# Noise.net
KiCad netlist of a schematic drawn in Altium Designer
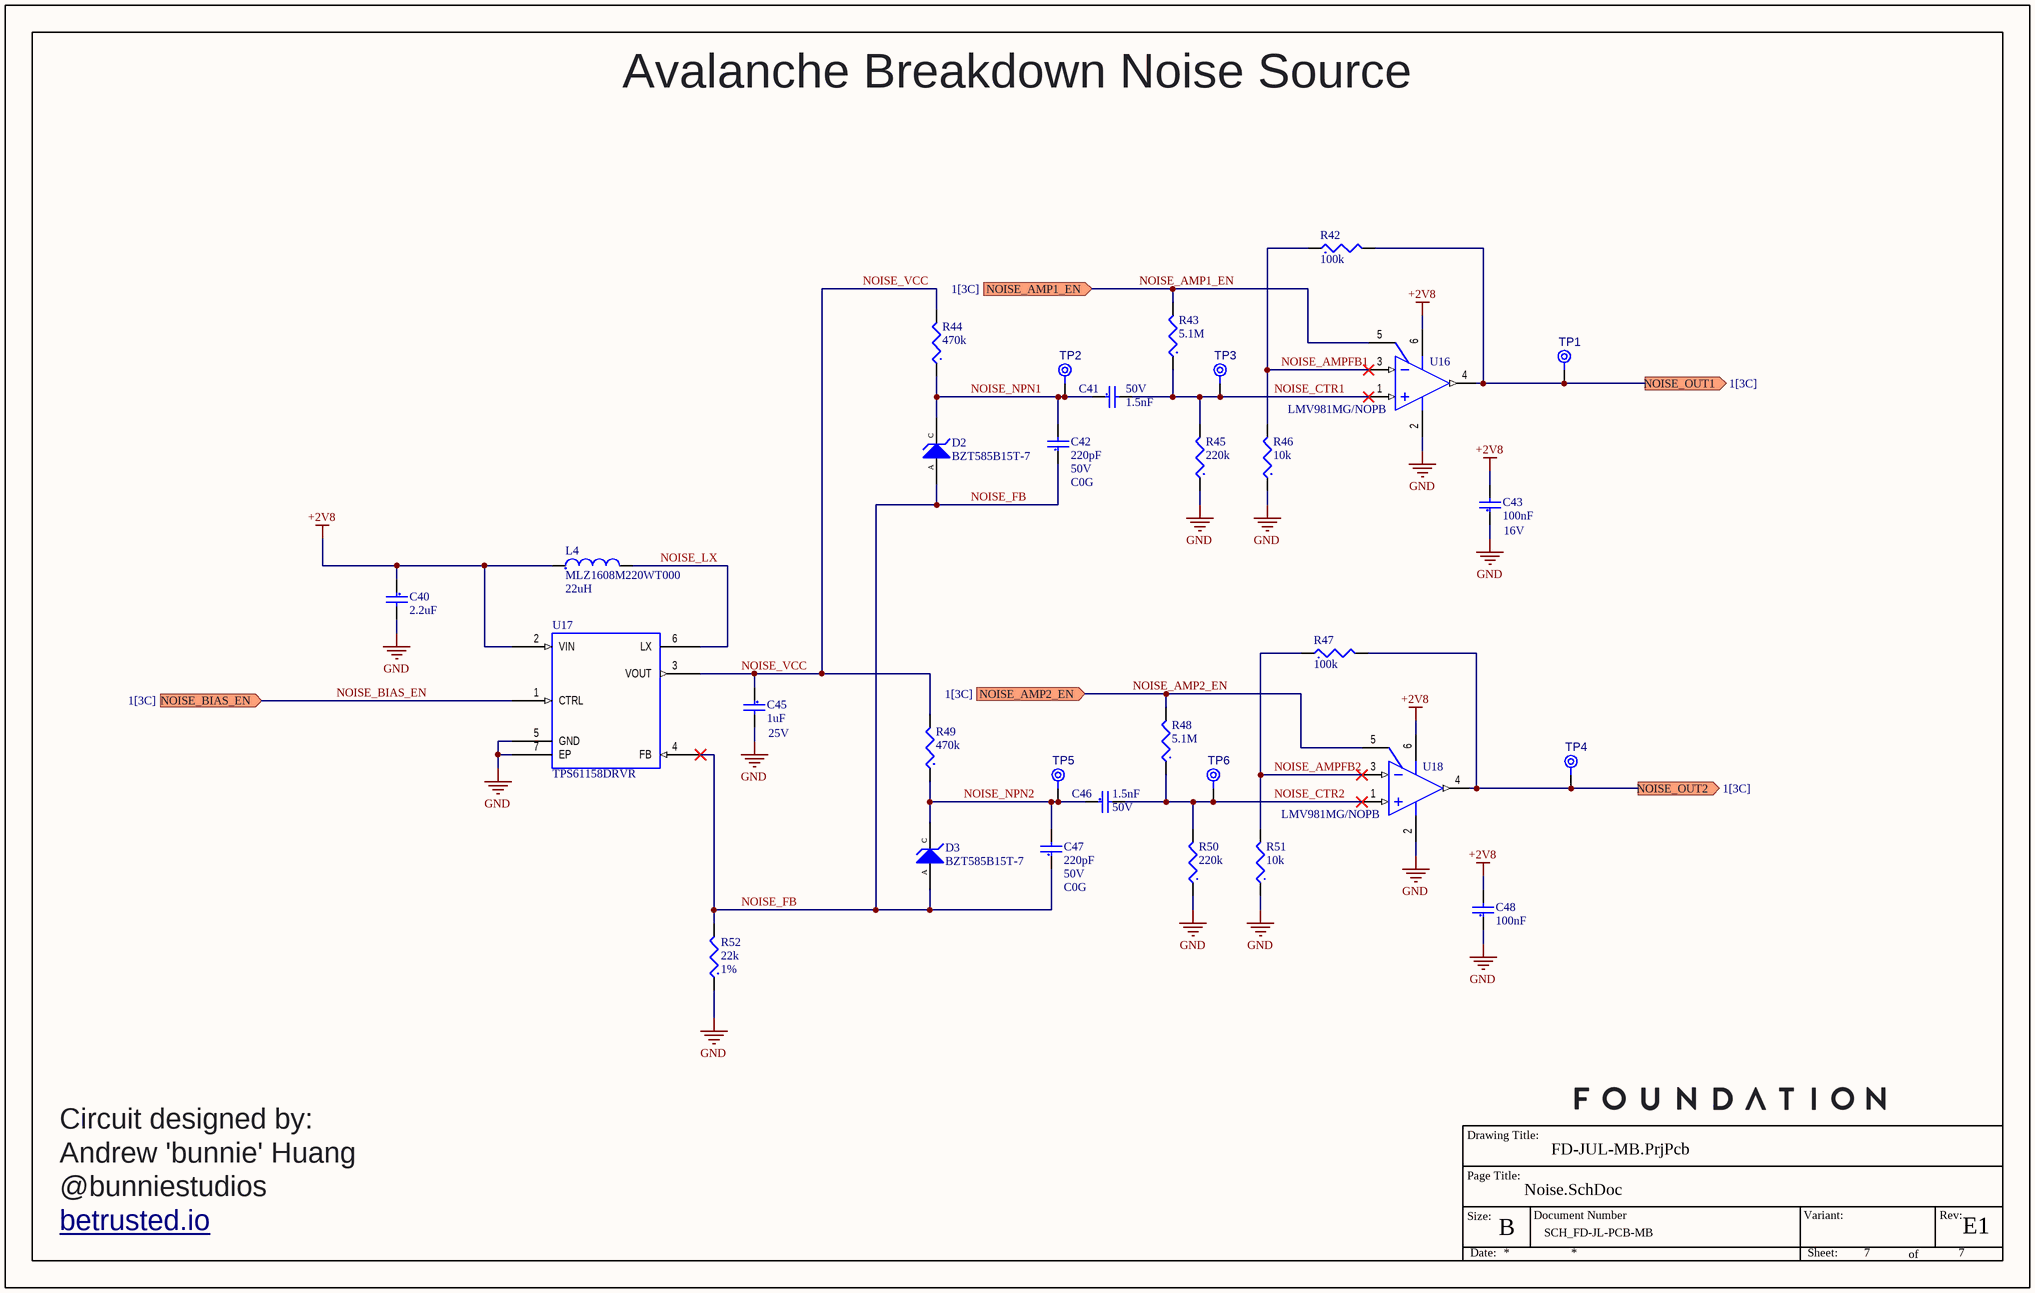
[diagram p0: Noise.SchDoc]

(export (version "E")
  (design (tool "Eeschema 10.0.6"))
  (components
    (comp (ref "C40")
      (value "CAP CER 2.2uF 6.3V 10% X5R 0402")
      (footprint "CAPC0402(1005)55_L")
      (description "2.2µF ±10% 6.3V Ceramic Capacitor X5R 0402 (1005 Metric)")
      (fields (field (name "CAPACITANCE") "2.2uF") (field (name "TOLERANCE") "10%"))
      (libsource (lib "Altium Concord Pro on A365") (part "CAP-NP-2"))
    )
    (comp (ref "C41")
      (value "CAP CER 1500pF 50V 10% X7R 0402")
      (footprint "CAPC0402(1005)55_L")
      (description "1500pF ±10% 50V Ceramic Capacitor X7R 0402 (1005 Metric)")
      (fields
        (field (name "CAPACITANCE") "1.5nF")
        (field (name "VOLTAGE") "50V")
        (field (name "VOLTAGE RATING") "50V")
        (field (name "TOLERANCE") "10%")
      )
      (libsource (lib "Altium Concord Pro on A365") (part "CAP-NP-2"))
    )
    (comp (ref "C42")
      (value "CAP CER 220pF 50V 5% C0G 0402")
      (footprint "CAPC0402(1005)55_L")
      (description "220pF ±5% 50V Ceramic Capacitor C0G, NP0 0402 (1005 Metric)")
      (fields
        (field (name "CAPACITANCE") "220pF")
        (field (name "VOLTAGE") "50V")
        (field (name "DIELECTRIC") "C0G")
        (field (name "TOLERANCE") "5%")
      )
      (libsource (lib "Altium Concord Pro on A365") (part "CAP-NP-2"))
    )
    (comp (ref "C43")
      (value "CAP CER 0.1uF 16V 10% X7R 0402")
      (footprint "CAPC0402(1005)55_L")
      (description "0.1µF ±10% 16V Ceramic Capacitor X7R 0402 (1005 Metric)")
      (fields
        (field (name "CAPACITANCE") "100nF")
        (field (name "VOLTAGE") "16V")
        (field (name "TOLERANCE") "10%")
      )
      (libsource (lib "Altium Concord Pro on A365") (part "CAP-NP-2"))
    )
    (comp (ref "C45")
      (value "CAP CER 1uF 25V 10% X5R 0402")
      (footprint "CAPC0402(1005)55_L")
      (description "±10% 25V Ceramic Capacitor X5R 0402 (1005 Metric)")
      (fields (field (name "CAPACITANCE") "1uF") (field (name "RATED DC VOLTAGE (URDC)") "25V"))
      (libsource (lib "Altium Concord Pro on A365") (part "CAP-NP-2"))
    )
    (comp (ref "C46")
      (value "CAP CER 1500pF 50V 10% X7R 0402")
      (footprint "CAPC0402(1005)55_L")
      (description "1500pF ±10% 50V Ceramic Capacitor X7R 0402 (1005 Metric)")
      (fields
        (field (name "CAPACITANCE") "1.5nF")
        (field (name "VOLTAGE") "50V")
        (field (name "TOLERANCE") "10%")
      )
      (libsource (lib "Altium Concord Pro on A365") (part "CAP-NP-2"))
    )
    (comp (ref "C47")
      (value "CAP CER 220pF 50V 5% C0G 0402")
      (footprint "CAPC0402(1005)55_L")
      (description "220pF ±5% 50V Ceramic Capacitor C0G, NP0 0402 (1005 Metric)")
      (fields
        (field (name "CAPACITANCE") "220pF")
        (field (name "VOLTAGE") "50V")
        (field (name "DIELECTRIC") "C0G")
        (field (name "TOLERANCE") "5%")
      )
      (libsource (lib "Altium Concord Pro on A365") (part "CAP-NP-2"))
    )
    (comp (ref "C48")
      (value "CAP CER 0.1uF 16V 10% X7R 0402")
      (footprint "CAPC0402(1005)55_L")
      (description "0.1µF ±10% 16V Ceramic Capacitor X7R 0402 (1005 Metric)")
      (fields
        (field (name "CAPACITANCE") "100nF")
        (field (name "VOLTAGE") "16V")
        (field (name "TOLERANCE") "10%")
      )
      (libsource (lib "Altium Concord Pro on A365") (part "CAP-NP-2"))
    )
    (comp (ref "D2")
      (value "BZT585B15T-7")
      (footprint "DIOD - SOD-523-2_L")
      (description "Zener Diode 15V 350mW ±2% Surface Mount SOD-523")
      (fields (field (name "TOLERANCE") "2%"))
      (libsource (lib "Altium Concord Pro on A365") (part "DZEN-AC-2"))
    )
    (comp (ref "D3")
      (value "BZT585B15T-7")
      (footprint "DIOD - SOD-523-2_L")
      (description "Zener Diode 15V 350mW ±2% Surface Mount SOD-523")
      (fields (field (name "TOLERANCE") "2%"))
      (libsource (lib "Altium Concord Pro on A365") (part "DZEN-AC-2"))
    )
    (comp (ref "L4")
      (value "MLZ1608M220WT000")
      (footprint "INDC0603(1608)90_L")
      (description "22µH Shielded Multilayer Inductor 150mA 2.4Ohm 0603 (1608 Metric)")
      (fields (field (name "INDUCTANCE") "22uH") (field (name "TOLERANCE") "20%"))
      (libsource (lib "Altium Concord Pro on A365") (part "IND-NP-2"))
    )
    (comp (ref "R42")
      (value "RES 100K 1/16W 1% 0402")
      (footprint "RESC0402(1005)_L")
      (description "100 kOhms ±1% 0.063W, 1/16W Chip Resistor 0402 (1005 Metric) Automotive AEC-Q200 Thick Film")
      (fields (field (name "RESISTANCE") "100k") (field (name "TOLERANCE") "1%"))
      (libsource (lib "Altium Concord Pro on A365") (part "RES-2"))
    )
    (comp (ref "R43")
      (value "RES 5.1M 1/16W 1% 0402")
      (footprint "RESC0402(1005)_L")
      (description "5.1 MOhms ±1% 0.1W, 1/10W Chip Resistor 0402 (1005 Metric)")
      (fields (field (name "RESISTANCE") "5.1M") (field (name "TOLERANCE") "1%"))
      (libsource (lib "Altium Concord Pro on A365") (part "RES-2"))
    )
    (comp (ref "R44")
      (value "RES 470K 1/16W 1% 0402")
      (footprint "RESC0402(1005)_L")
      (description "470 kOhms ±1% 0.063W, 1/16W Chip Resistor 0402 (1005 Metric)")
      (fields (field (name "RESISTANCE") "470k") (field (name "TOLERANCE") "1%"))
      (libsource (lib "Altium Concord Pro on A365") (part "RES-2"))
    )
    (comp (ref "R45")
      (value "RES 220K 1/16W 1% 0402")
      (footprint "RESC0402(1005)_L")
      (description "220 kOhms ±1% 0.063W, 1/16W Chip Resistor 0402 (1005 Metric)")
      (fields (field (name "RESISTANCE") "220k") (field (name "TOLERANCE") "1%"))
      (libsource (lib "Altium Concord Pro on A365") (part "RES-2"))
    )
    (comp (ref "R46")
      (value "RES 10K 1/16W 1% 0402")
      (footprint "RESC0402(1005)_L")
      (description "10 kOhms ±1% 0.063W, 1/16W Chip Resistor 0402 (1005 Metric)")
      (fields (field (name "RESISTANCE") "10k") (field (name "TOLERANCE") "1%"))
      (libsource (lib "Altium Concord Pro on A365") (part "RES-2"))
    )
    (comp (ref "R47")
      (value "RES 100K 1/16W 1% 0402")
      (footprint "RESC0402(1005)_L")
      (description "100 kOhms ±1% 0.063W, 1/16W Chip Resistor 0402 (1005 Metric) Automotive AEC-Q200 Thick Film")
      (fields (field (name "RESISTANCE") "100k") (field (name "TOLERANCE") "1%"))
      (libsource (lib "Altium Concord Pro on A365") (part "RES-2"))
    )
    (comp (ref "R48")
      (value "RES 5.1M 1/16W 1% 0402")
      (footprint "RESC0402(1005)_L")
      (description "5.1 MOhms ±1% 0.1W, 1/10W Chip Resistor 0402 (1005 Metric)")
      (fields (field (name "RESISTANCE") "5.1M") (field (name "TOLERANCE") "1%"))
      (libsource (lib "Altium Concord Pro on A365") (part "RES-2"))
    )
    (comp (ref "R49")
      (value "RES 470K 1/16W 1% 0402")
      (footprint "RESC0402(1005)_L")
      (description "470 kOhms ±1% 0.063W, 1/16W Chip Resistor 0402 (1005 Metric)")
      (fields (field (name "RESISTANCE") "470k") (field (name "TOLERANCE") "1%"))
      (libsource (lib "Altium Concord Pro on A365") (part "RES-2"))
    )
    (comp (ref "R50")
      (value "RES 220K 1/16W 1% 0402")
      (footprint "RESC0402(1005)_L")
      (description "220 kOhms ±1% 0.063W, 1/16W Chip Resistor 0402 (1005 Metric)")
      (fields (field (name "RESISTANCE") "220k") (field (name "TOLERANCE") "1%"))
      (libsource (lib "Altium Concord Pro on A365") (part "RES-2"))
    )
    (comp (ref "R51")
      (value "RES 10K 1/16W 1% 0402")
      (footprint "RESC0402(1005)_L")
      (description "10 kOhms ±1% 0.063W, 1/16W Chip Resistor 0402 (1005 Metric)")
      (fields (field (name "RESISTANCE") "10k") (field (name "TOLERANCE") "1%"))
      (libsource (lib "Altium Concord Pro on A365") (part "RES-2"))
    )
    (comp (ref "R52")
      (value "RES 22K 1/16W 1% 0402")
      (footprint "RESC0402(1005)_L")
      (description "22 kOhms ±1% 0.063W, 1/16W Chip Resistor 0402 (1005 Metric)")
      (fields (field (name "RESISTANCE") "22k") (field (name "TOLERANCE") "1%"))
      (libsource (lib "Altium Concord Pro on A365") (part "RES-2"))
    )
    (comp (ref "TP1")
      (value "TPAD8R")
      (footprint "TP08R")
      (description "0.8mm round")
      (libsource (lib "Altium Concord Pro on A365") (part "TP-R-1"))
    )
    (comp (ref "TP2")
      (value "TPAD8R")
      (footprint "TP08R")
      (description "0.8mm round")
      (libsource (lib "Altium Concord Pro on A365") (part "TP-R-1"))
    )
    (comp (ref "TP3")
      (value "TPAD8R")
      (footprint "TP08R")
      (description "0.8mm round")
      (libsource (lib "Altium Concord Pro on A365") (part "TP-R-1"))
    )
    (comp (ref "TP4")
      (value "TPAD8R")
      (footprint "TP08R")
      (description "0.8mm round")
      (libsource (lib "Altium Concord Pro on A365") (part "TP-R-1"))
    )
    (comp (ref "TP5")
      (value "TPAD8R")
      (footprint "TP08R")
      (description "0.8mm round")
      (libsource (lib "Altium Concord Pro on A365") (part "TP-R-1"))
    )
    (comp (ref "TP6")
      (value "TPAD8R")
      (footprint "TP08R")
      (description "0.8mm round")
      (libsource (lib "Altium Concord Pro on A365") (part "TP-R-1"))
    )
    (comp (ref "U16")
      (value "LMV981MG/NOPB")
      (footprint "TI - SC70-6_L")
      (description "General Purpose Amplifier 1 Circuit Rail-to-Rail SC-70-6")
      (libsource (lib "Altium Concord Pro on A365") (part "AMP-OPA-LMV981-6"))
    )
    (comp (ref "U17")
      (value "TPS61158DRVR")
      (footprint "TI - WSON-6_L")
      (description "LED Driver IC 1 Output DC DC Regulator Step-Up (Boost) PWM Dimming 30mA 6-WSON (2x2)")
      (libsource (lib "Altium Concord Pro on A365") (part "TPS61158DRVR"))
    )
    (comp (ref "U18")
      (value "LMV981MG/NOPB")
      (footprint "TI - SC70-6_L")
      (description "General Purpose Amplifier 1 Circuit Rail-to-Rail SC-70-6")
      (libsource (lib "Altium Concord Pro on A365") (part "AMP-OPA-LMV981-6"))
    )
  )
  (nets
    (net (code "1") (name "+2V8") (class "Default")
      (node (ref "C40") (pin "1") (pinfunction "1_1") (pintype "passive"))
      (node (ref "C43") (pin "2") (pinfunction "2_2") (pintype "passive"))
      (node (ref "C48") (pin "2") (pinfunction "2_2") (pintype "passive"))
      (node (ref "L4") (pin "1") (pinfunction "1_1") (pintype "passive"))
      (node (ref "U16") (pin "6") (pinfunction "VDD_6") (pintype "power_in"))
      (node (ref "U17") (pin "2") (pinfunction "VIN_2") (pintype "input"))
      (node (ref "U18") (pin "6") (pinfunction "VDD_6") (pintype "power_in"))
    )
    (net (code "2") (name "/NOISE_AMP1_EN") (class "Default")
      (node (ref "R43") (pin "2") (pinfunction "2_2") (pintype "passive"))
      (node (ref "U16") (pin "5") (pinfunction "~{SHDN}_5") (pintype "passive"))
    )
    (net (code "3") (name "/NOISE_AMP2_EN") (class "Default")
      (node (ref "R48") (pin "2") (pinfunction "2_2") (pintype "passive"))
      (node (ref "U18") (pin "5") (pinfunction "~{SHDN}_5") (pintype "passive"))
    )
    (net (code "4") (name "/NOISE_AMPFB1") (class "Default")
      (node (ref "R42") (pin "1") (pinfunction "1_1") (pintype "passive"))
      (node (ref "R46") (pin "2") (pinfunction "2_2") (pintype "passive"))
      (node (ref "U16") (pin "3") (pinfunction "IN-_3") (pintype "input"))
    )
    (net (code "5") (name "/NOISE_AMPFB2") (class "Default")
      (node (ref "R47") (pin "1") (pinfunction "1_1") (pintype "passive"))
      (node (ref "R51") (pin "2") (pinfunction "2_2") (pintype "passive"))
      (node (ref "U18") (pin "3") (pinfunction "IN-_3") (pintype "input"))
    )
    (net (code "6") (name "/NOISE_BIAS_EN") (class "Default")
      (node (ref "U17") (pin "1") (pinfunction "CTRL_1") (pintype "input"))
    )
    (net (code "7") (name "/NOISE_CTR1") (class "Default")
      (node (ref "C41") (pin "2") (pinfunction "2_2") (pintype "passive"))
      (node (ref "R43") (pin "1") (pinfunction "1_1") (pintype "passive"))
      (node (ref "R45") (pin "2") (pinfunction "2_2") (pintype "passive"))
      (node (ref "TP3") (pin "1") (pinfunction "TP_1") (pintype "passive"))
      (node (ref "U16") (pin "1") (pinfunction "IN+_1") (pintype "input"))
    )
    (net (code "8") (name "/NOISE_CTR2") (class "Default")
      (node (ref "C46") (pin "2") (pinfunction "2_2") (pintype "passive"))
      (node (ref "R48") (pin "1") (pinfunction "1_1") (pintype "passive"))
      (node (ref "R50") (pin "2") (pinfunction "2_2") (pintype "passive"))
      (node (ref "TP6") (pin "1") (pinfunction "TP_1") (pintype "passive"))
      (node (ref "U18") (pin "1") (pinfunction "IN+_1") (pintype "input"))
    )
    (net (code "9") (name "/NOISE_FB") (class "Default")
      (node (ref "C42") (pin "1") (pinfunction "1_1") (pintype "passive"))
      (node (ref "C47") (pin "1") (pinfunction "1_1") (pintype "passive"))
      (node (ref "D2") (pin "A") (pinfunction "A_A") (pintype "passive"))
      (node (ref "D3") (pin "A") (pinfunction "A_A") (pintype "passive"))
      (node (ref "R52") (pin "2") (pinfunction "2_2") (pintype "passive"))
      (node (ref "U17") (pin "4") (pinfunction "FB_4") (pintype "input"))
    )
    (net (code "10") (name "/NOISE_LX") (class "Default")
      (node (ref "L4") (pin "2") (pinfunction "2_2") (pintype "passive"))
      (node (ref "U17") (pin "6") (pinfunction "LX_6") (pintype "passive"))
    )
    (net (code "11") (name "/NOISE_NPN1") (class "Default")
      (node (ref "C41") (pin "1") (pinfunction "1_1") (pintype "passive"))
      (node (ref "C42") (pin "2") (pinfunction "2_2") (pintype "passive"))
      (node (ref "D2") (pin "C") (pinfunction "C_C") (pintype "passive"))
      (node (ref "R44") (pin "1") (pinfunction "1_1") (pintype "passive"))
      (node (ref "TP2") (pin "1") (pinfunction "TP_1") (pintype "passive"))
    )
    (net (code "12") (name "/NOISE_NPN2") (class "Default")
      (node (ref "C46") (pin "1") (pinfunction "1_1") (pintype "passive"))
      (node (ref "C47") (pin "2") (pinfunction "2_2") (pintype "passive"))
      (node (ref "D3") (pin "C") (pinfunction "C_C") (pintype "passive"))
      (node (ref "R49") (pin "1") (pinfunction "1_1") (pintype "passive"))
      (node (ref "TP5") (pin "1") (pinfunction "TP_1") (pintype "passive"))
    )
    (net (code "13") (name "/NOISE_OUT1") (class "Default")
      (node (ref "R42") (pin "2") (pinfunction "2_2") (pintype "passive"))
      (node (ref "TP1") (pin "1") (pinfunction "TP_1") (pintype "passive"))
      (node (ref "U16") (pin "4") (pinfunction "OUT_4") (pintype "output"))
    )
    (net (code "14") (name "/NOISE_OUT2") (class "Default")
      (node (ref "R47") (pin "2") (pinfunction "2_2") (pintype "passive"))
      (node (ref "TP4") (pin "1") (pinfunction "TP_1") (pintype "passive"))
      (node (ref "U18") (pin "4") (pinfunction "OUT_4") (pintype "output"))
    )
    (net (code "15") (name "/NOISE_VCC") (class "Default")
      (node (ref "C45") (pin "1") (pinfunction "1_1") (pintype "passive"))
      (node (ref "R44") (pin "2") (pinfunction "2_2") (pintype "passive"))
      (node (ref "R49") (pin "2") (pinfunction "2_2") (pintype "passive"))
      (node (ref "U17") (pin "3") (pinfunction "VOUT_3") (pintype "output"))
    )
    (net (code "16") (name "GND") (class "Default")
      (node (ref "C40") (pin "2") (pinfunction "2_2") (pintype "passive"))
      (node (ref "C43") (pin "1") (pinfunction "1_1") (pintype "passive"))
      (node (ref "C45") (pin "2") (pinfunction "2_2") (pintype "passive"))
      (node (ref "C48") (pin "1") (pinfunction "1_1") (pintype "passive"))
      (node (ref "R45") (pin "1") (pinfunction "1_1") (pintype "passive"))
      (node (ref "R46") (pin "1") (pinfunction "1_1") (pintype "passive"))
      (node (ref "R50") (pin "1") (pinfunction "1_1") (pintype "passive"))
      (node (ref "R51") (pin "1") (pinfunction "1_1") (pintype "passive"))
      (node (ref "R52") (pin "1") (pinfunction "1_1") (pintype "passive"))
      (node (ref "U16") (pin "2") (pinfunction "GND_2") (pintype "power_in"))
      (node (ref "U17") (pin "5") (pinfunction "GND_5") (pintype "power_in"))
      (node (ref "U17") (pin "7") (pinfunction "EP_7") (pintype "power_in"))
      (node (ref "U18") (pin "2") (pinfunction "GND_2") (pintype "power_in"))
    )
  )
)
